# VoltageConverter.net
KiCad netlist of a schematic drawn in EAGLE
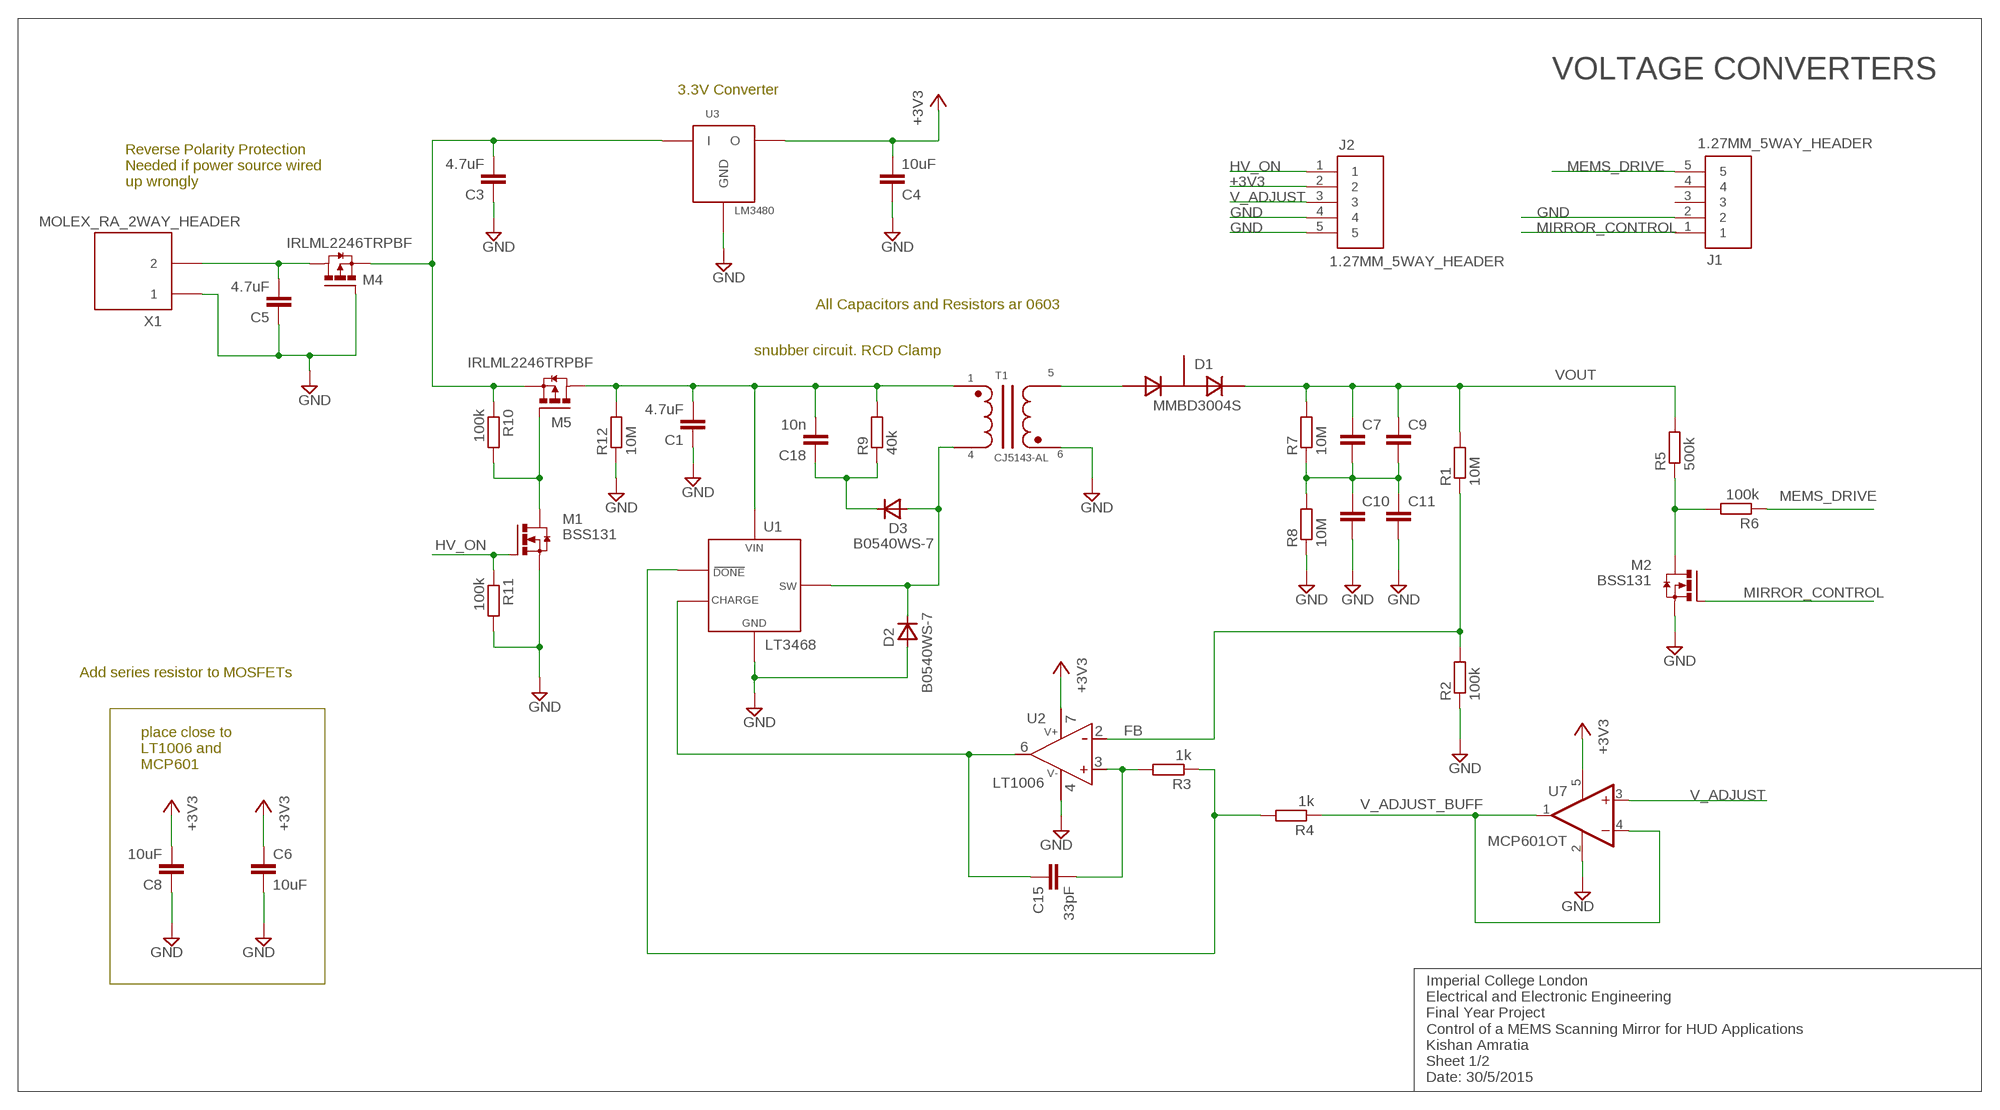
[diagram p0: schematic, sheet 1]

(export (version "E")
  (design (tool "Eeschema 10.0.6"))
  (components
    (comp (ref "C1")
      (value "4.7uF")
      (footprint "eagle-import:C0603K")
      (libsource (lib "eagle-import") (part "C-EUC0603K"))
    )
    (comp (ref "C3")
      (value "4.7uF")
      (footprint "eagle-import:C0603K")
      (libsource (lib "eagle-import") (part "C-EUC0603K"))
    )
    (comp (ref "C4")
      (value "10uF")
      (footprint "eagle-import:C0603")
      (libsource (lib "eagle-import") (part "C-EUC0603"))
    )
    (comp (ref "C5")
      (value "4.7uF")
      (footprint "eagle-import:C0603K")
      (libsource (lib "eagle-import") (part "C-EUC0603K"))
    )
    (comp (ref "C6")
      (value "10uF")
      (footprint "eagle-import:C0603")
      (libsource (lib "eagle-import") (part "C-EUC0603"))
    )
    (comp (ref "C7")
      (value "C-EUC2220K")
      (footprint "eagle-import:C2220K")
      (libsource (lib "eagle-import") (part "C-EUC2220K"))
    )
    (comp (ref "C8")
      (value "10uF")
      (footprint "eagle-import:C0603")
      (libsource (lib "eagle-import") (part "C-EUC0603"))
    )
    (comp (ref "C9")
      (value "C-EUC2220K")
      (footprint "eagle-import:C2220K")
      (libsource (lib "eagle-import") (part "C-EUC2220K"))
    )
    (comp (ref "C10")
      (value "C-EUC2220K")
      (footprint "eagle-import:C2220K")
      (libsource (lib "eagle-import") (part "C-EUC2220K"))
    )
    (comp (ref "C11")
      (value "C-EUC2220K")
      (footprint "eagle-import:C2220K")
      (libsource (lib "eagle-import") (part "C-EUC2220K"))
    )
    (comp (ref "C15")
      (value "33pF")
      (footprint "eagle-import:C0603")
      (libsource (lib "eagle-import") (part "C-EUC0603"))
    )
    (comp (ref "C18")
      (value "10n")
      (footprint "eagle-import:C0603K")
      (libsource (lib "eagle-import") (part "C-EUC0603K"))
    )
    (comp (ref "D1")
      (value "MMBD3004S")
      (footprint "eagle-import:SOT-23")
      (libsource (lib "eagle-import") (part "MMBD3004S"))
    )
    (comp (ref "D2")
      (value "B0540WS-7")
      (footprint "eagle-import:SOD-323")
      (libsource (lib "eagle-import") (part "B0540WS-7"))
    )
    (comp (ref "D3")
      (value "B0540WS-7")
      (footprint "eagle-import:SOD-323")
      (libsource (lib "eagle-import") (part "B0540WS-7"))
    )
    (comp (ref "J1")
      (value "1.27MM_5WAY_HEADER")
      (footprint "eagle-import:1.27MM_5WAY_HEADER")
      (libsource (lib "eagle-import") (part "1.27MM_5WAY_HEADER"))
    )
    (comp (ref "J2")
      (value "1.27MM_5WAY_HEADER")
      (footprint "eagle-import:1.27MM_5WAY_HEADER")
      (libsource (lib "eagle-import") (part "1.27MM_5WAY_HEADER"))
    )
    (comp (ref "M1")
      (value "BSS131")
      (footprint "eagle-import:SOT-23")
      (libsource (lib "eagle-import") (part "BSS131"))
    )
    (comp (ref "M2")
      (value "BSS131")
      (footprint "eagle-import:SOT-23")
      (libsource (lib "eagle-import") (part "BSS131"))
    )
    (comp (ref "M4")
      (value "IRLML2246TRPBF")
      (footprint "eagle-import:SOT-23")
      (libsource (lib "eagle-import") (part "IRLML2246TRPBF"))
    )
    (comp (ref "M5")
      (value "IRLML2246TRPBF")
      (footprint "eagle-import:SOT-23")
      (libsource (lib "eagle-import") (part "IRLML2246TRPBF"))
    )
    (comp (ref "R1")
      (value "10M")
      (footprint "eagle-import:R0603")
      (libsource (lib "eagle-import") (part "R-EU_R0603"))
    )
    (comp (ref "R2")
      (value "100k")
      (footprint "eagle-import:R0603")
      (libsource (lib "eagle-import") (part "R-EU_R0603"))
    )
    (comp (ref "R3")
      (value "1k")
      (footprint "eagle-import:R0603")
      (libsource (lib "eagle-import") (part "R-EU_R0603"))
    )
    (comp (ref "R4")
      (value "1k")
      (footprint "eagle-import:R0603")
      (libsource (lib "eagle-import") (part "R-EU_R0603"))
    )
    (comp (ref "R5")
      (value "500k")
      (footprint "eagle-import:R0603")
      (libsource (lib "eagle-import") (part "R-EU_R0603"))
    )
    (comp (ref "R6")
      (value "100k")
      (footprint "eagle-import:R0603")
      (libsource (lib "eagle-import") (part "R-EU_R0603"))
    )
    (comp (ref "R7")
      (value "10M")
      (footprint "eagle-import:R0603")
      (libsource (lib "eagle-import") (part "R-EU_R0603"))
    )
    (comp (ref "R8")
      (value "10M")
      (footprint "eagle-import:R0603")
      (libsource (lib "eagle-import") (part "R-EU_R0603"))
    )
    (comp (ref "R9")
      (value "40k")
      (footprint "eagle-import:R0603")
      (libsource (lib "eagle-import") (part "R-EU_R0603"))
    )
    (comp (ref "R10")
      (value "100k")
      (footprint "eagle-import:R0603")
      (libsource (lib "eagle-import") (part "R-EU_R0603"))
    )
    (comp (ref "R11")
      (value "100k")
      (footprint "eagle-import:R0603")
      (libsource (lib "eagle-import") (part "R-EU_R0603"))
    )
    (comp (ref "R12")
      (value "10M")
      (footprint "eagle-import:R0603")
      (libsource (lib "eagle-import") (part "R-EU_R0603"))
    )
    (comp (ref "T1")
      (value "CJ5143-AL")
      (footprint "eagle-import:CJ45143-AL")
      (libsource (lib "eagle-import") (part "CJ5143-AL"))
    )
    (comp (ref "U1")
      (value "LT3468")
      (footprint "eagle-import:TSOT-23")
      (libsource (lib "eagle-import") (part "LT3468"))
    )
    (comp (ref "U2")
      (value "LT1006")
      (footprint "eagle-import:SOIC127P600X175-8N")
      (libsource (lib "eagle-import") (part "LT1006"))
    )
    (comp (ref "U3")
      (value "LM3480")
      (footprint "eagle-import:SOT-23")
      (libsource (lib "eagle-import") (part "LM3480"))
    )
    (comp (ref "U7")
      (value "MCP601OT")
      (footprint "eagle-import:SOT23-5")
      (libsource (lib "eagle-import") (part "MCP601OT"))
    )
    (comp (ref "X1")
      (value "MOLEX_RA_2WAY_HEADER")
      (footprint "eagle-import:MOLEX_RA_2WAY_HEADER")
      (libsource (lib "eagle-import") (part "MOLEX_RA_2WAY_HEADER"))
    )
  )
  (nets
    (net (code "1") (name "+3V3") (class "Default")
      (node (ref "C4") (pin "2") (pinfunction "2_2") (pintype "passive"))
      (node (ref "C6") (pin "1") (pinfunction "1_1") (pintype "passive"))
      (node (ref "C8") (pin "2") (pinfunction "2_2") (pintype "passive"))
      (node (ref "J2") (pin "2") (pinfunction "2_2") (pintype "bidirectional"))
      (node (ref "U2") (pin "7") (pinfunction "7_7") (pintype "bidirectional"))
      (node (ref "U3") (pin "A") (pinfunction "O_A") (pintype "bidirectional"))
      (node (ref "U7") (pin "5") (pinfunction "V+_5") (pintype "power_in"))
    )
    (net (code "2") (name "/FB") (class "Default")
      (node (ref "R1") (pin "1") (pinfunction "1_1") (pintype "passive"))
      (node (ref "R2") (pin "2") (pinfunction "2_2") (pintype "passive"))
      (node (ref "U2") (pin "2") (pinfunction "2_2") (pintype "bidirectional"))
    )
    (net (code "3") (name "/HV_ON") (class "Default")
      (node (ref "J2") (pin "1") (pinfunction "1_1") (pintype "bidirectional"))
      (node (ref "M1") (pin "A") (pinfunction "G_A") (pintype "passive"))
      (node (ref "R11") (pin "1") (pinfunction "1_1") (pintype "passive"))
    )
    (net (code "4") (name "/MEMS_DRIVE") (class "Default")
      (node (ref "J1") (pin "5") (pinfunction "5_5") (pintype "bidirectional"))
      (node (ref "R6") (pin "1") (pinfunction "1_1") (pintype "passive"))
    )
    (net (code "5") (name "/MIRROR_CONTROL") (class "Default")
      (node (ref "J1") (pin "1") (pinfunction "1_1") (pintype "bidirectional"))
      (node (ref "M2") (pin "A") (pinfunction "G_A") (pintype "passive"))
    )
    (net (code "6") (name "/VOUT") (class "Default")
      (node (ref "C7") (pin "1") (pinfunction "1_1") (pintype "passive"))
      (node (ref "C9") (pin "1") (pinfunction "1_1") (pintype "passive"))
      (node (ref "D1") (pin "K") (pinfunction "K_K") (pintype "bidirectional"))
      (node (ref "R1") (pin "2") (pinfunction "2_2") (pintype "passive"))
      (node (ref "R5") (pin "2") (pinfunction "2_2") (pintype "passive"))
      (node (ref "R7") (pin "2") (pinfunction "2_2") (pintype "passive"))
    )
    (net (code "7") (name "/V_ADJUST") (class "Default")
      (node (ref "J2") (pin "3") (pinfunction "3_3") (pintype "bidirectional"))
      (node (ref "U7") (pin "3") (pinfunction "+IN_3") (pintype "input"))
    )
    (net (code "8") (name "/V_ADJUST_BUFF") (class "Default")
      (node (ref "R4") (pin "1") (pinfunction "1_1") (pintype "passive"))
      (node (ref "U7") (pin "1") (pinfunction "OUT_1") (pintype "output"))
      (node (ref "U7") (pin "4") (pinfunction "-IN_4") (pintype "input"))
    )
    (net (code "9") (name "GND") (class "Default")
      (node (ref "C1") (pin "1") (pinfunction "1_1") (pintype "passive"))
      (node (ref "C10") (pin "2") (pinfunction "2_2") (pintype "passive"))
      (node (ref "C11") (pin "2") (pinfunction "2_2") (pintype "passive"))
      (node (ref "C3") (pin "1") (pinfunction "1_1") (pintype "passive"))
      (node (ref "C4") (pin "1") (pinfunction "1_1") (pintype "passive"))
      (node (ref "C5") (pin "1") (pinfunction "1_1") (pintype "passive"))
      (node (ref "C6") (pin "2") (pinfunction "2_2") (pintype "passive"))
      (node (ref "C8") (pin "1") (pinfunction "1_1") (pintype "passive"))
      (node (ref "D2") (pin "A") (pinfunction "A_A") (pintype "bidirectional"))
      (node (ref "J1") (pin "2") (pinfunction "2_2") (pintype "bidirectional"))
      (node (ref "J2") (pin "4") (pinfunction "4_4") (pintype "bidirectional"))
      (node (ref "J2") (pin "5") (pinfunction "5_5") (pintype "bidirectional"))
      (node (ref "M1") (pin "K") (pinfunction "S_K") (pintype "passive"))
      (node (ref "M2") (pin "K") (pinfunction "S_K") (pintype "passive"))
      (node (ref "M4") (pin "A") (pinfunction "G_A") (pintype "passive"))
      (node (ref "R11") (pin "2") (pinfunction "2_2") (pintype "passive"))
      (node (ref "R12") (pin "1") (pinfunction "1_1") (pintype "passive"))
      (node (ref "R2") (pin "1") (pinfunction "1_1") (pintype "passive"))
      (node (ref "R8") (pin "1") (pinfunction "1_1") (pintype "passive"))
      (node (ref "T1") (pin "5") (pinfunction "5_5") (pintype "bidirectional"))
      (node (ref "U1") (pin "2") (pinfunction "2_2") (pintype "output"))
      (node (ref "U2") (pin "4") (pinfunction "4_4") (pintype "bidirectional"))
      (node (ref "U3") (pin "K1A2") (pinfunction "GND_K1A2") (pintype "bidirectional"))
      (node (ref "U7") (pin "2") (pinfunction "V-_2") (pintype "power_in"))
      (node (ref "X1") (pin "P$1") (pinfunction "1_P$1") (pintype "bidirectional"))
    )
    (net (code "10") (name "Net-(C10-Pad1)") (class "Default")
      (node (ref "C10") (pin "1") (pinfunction "1_1") (pintype "passive"))
      (node (ref "C11") (pin "1") (pinfunction "1_1") (pintype "passive"))
      (node (ref "C7") (pin "2") (pinfunction "2_2") (pintype "passive"))
      (node (ref "C9") (pin "2") (pinfunction "2_2") (pintype "passive"))
      (node (ref "R7") (pin "1") (pinfunction "1_1") (pintype "passive"))
      (node (ref "R8") (pin "2") (pinfunction "2_2") (pintype "passive"))
    )
    (net (code "11") (name "Net-(C15-Pad1)") (class "Default")
      (node (ref "C15") (pin "1") (pinfunction "1_1") (pintype "passive"))
      (node (ref "U1") (pin "4") (pinfunction "4_4") (pintype "output"))
      (node (ref "U2") (pin "6") (pinfunction "6_6") (pintype "bidirectional"))
    )
    (net (code "12") (name "Net-(C15-Pad2)") (class "Default")
      (node (ref "C15") (pin "2") (pinfunction "2_2") (pintype "passive"))
      (node (ref "R3") (pin "2") (pinfunction "2_2") (pintype "passive"))
      (node (ref "U2") (pin "3") (pinfunction "3_3") (pintype "bidirectional"))
    )
    (net (code "13") (name "Net-(C18-Pad1)") (class "Default")
      (node (ref "C18") (pin "1") (pinfunction "1_1") (pintype "passive"))
      (node (ref "D3") (pin "K") (pinfunction "K_K") (pintype "bidirectional"))
      (node (ref "R9") (pin "1") (pinfunction "1_1") (pintype "passive"))
    )
    (net (code "14") (name "Net-(D1-PadA)") (class "Default")
      (node (ref "D1") (pin "A") (pinfunction "A_A") (pintype "bidirectional"))
      (node (ref "T1") (pin "6") (pinfunction "6_6") (pintype "bidirectional"))
    )
    (net (code "15") (name "Net-(D2-PadK)") (class "Default")
      (node (ref "D2") (pin "K") (pinfunction "K_K") (pintype "bidirectional"))
      (node (ref "D3") (pin "A") (pinfunction "A_A") (pintype "bidirectional"))
      (node (ref "T1") (pin "4") (pinfunction "4_4") (pintype "bidirectional"))
      (node (ref "U1") (pin "1") (pinfunction "1_1") (pintype "output"))
    )
    (net (code "16") (name "Net-(M1-D)") (class "Default")
      (node (ref "M1") (pin "K1A2") (pinfunction "D_K1A2") (pintype "passive"))
      (node (ref "M5") (pin "A") (pinfunction "G_A") (pintype "passive"))
      (node (ref "R10") (pin "2") (pinfunction "2_2") (pintype "passive"))
    )
    (net (code "17") (name "Net-(M2-D)") (class "Default")
      (node (ref "M2") (pin "K1A2") (pinfunction "D_K1A2") (pintype "passive"))
      (node (ref "R5") (pin "1") (pinfunction "1_1") (pintype "passive"))
      (node (ref "R6") (pin "2") (pinfunction "2_2") (pintype "passive"))
    )
    (net (code "18") (name "Net-(M4-D)") (class "Default")
      (node (ref "C5") (pin "2") (pinfunction "2_2") (pintype "passive"))
      (node (ref "M4") (pin "K1A2") (pinfunction "D_K1A2") (pintype "passive"))
      (node (ref "X1") (pin "P$2") (pinfunction "2_P$2") (pintype "bidirectional"))
    )
    (net (code "19") (name "Net-(M4-S)") (class "Default")
      (node (ref "C3") (pin "2") (pinfunction "2_2") (pintype "passive"))
      (node (ref "M4") (pin "K") (pinfunction "S_K") (pintype "passive"))
      (node (ref "M5") (pin "K") (pinfunction "S_K") (pintype "passive"))
      (node (ref "R10") (pin "1") (pinfunction "1_1") (pintype "passive"))
      (node (ref "U3") (pin "K") (pinfunction "I_K") (pintype "bidirectional"))
    )
    (net (code "20") (name "Net-(M5-D)") (class "Default")
      (node (ref "C1") (pin "2") (pinfunction "2_2") (pintype "passive"))
      (node (ref "C18") (pin "2") (pinfunction "2_2") (pintype "passive"))
      (node (ref "M5") (pin "K1A2") (pinfunction "D_K1A2") (pintype "passive"))
      (node (ref "R12") (pin "2") (pinfunction "2_2") (pintype "passive"))
      (node (ref "R9") (pin "2") (pinfunction "2_2") (pintype "passive"))
      (node (ref "T1") (pin "1") (pinfunction "1_1") (pintype "bidirectional"))
      (node (ref "U1") (pin "5") (pinfunction "5_5") (pintype "output"))
    )
    (net (code "21") (name "Net-(R3-Pad1)") (class "Default")
      (node (ref "R3") (pin "1") (pinfunction "1_1") (pintype "passive"))
      (node (ref "R4") (pin "2") (pinfunction "2_2") (pintype "passive"))
      (node (ref "U1") (pin "3") (pinfunction "3_3") (pintype "output"))
    )
    (net (code "22") (name "unconnected-(D1-PadK1A2)") (class "Default")
      (node (ref "D1") (pin "K1A2") (pinfunction "K1A2_K1A2") (pintype "bidirectional"))
    )
    (net (code "23") (name "unconnected-(J1-Pad3)") (class "Default")
      (node (ref "J1") (pin "3") (pinfunction "3_3") (pintype "bidirectional"))
    )
    (net (code "24") (name "unconnected-(J1-Pad4)") (class "Default")
      (node (ref "J1") (pin "4") (pinfunction "4_4") (pintype "bidirectional"))
    )
  )
)
